# StabTracker.net
KiCad netlist of a schematic drawn in EAGLE
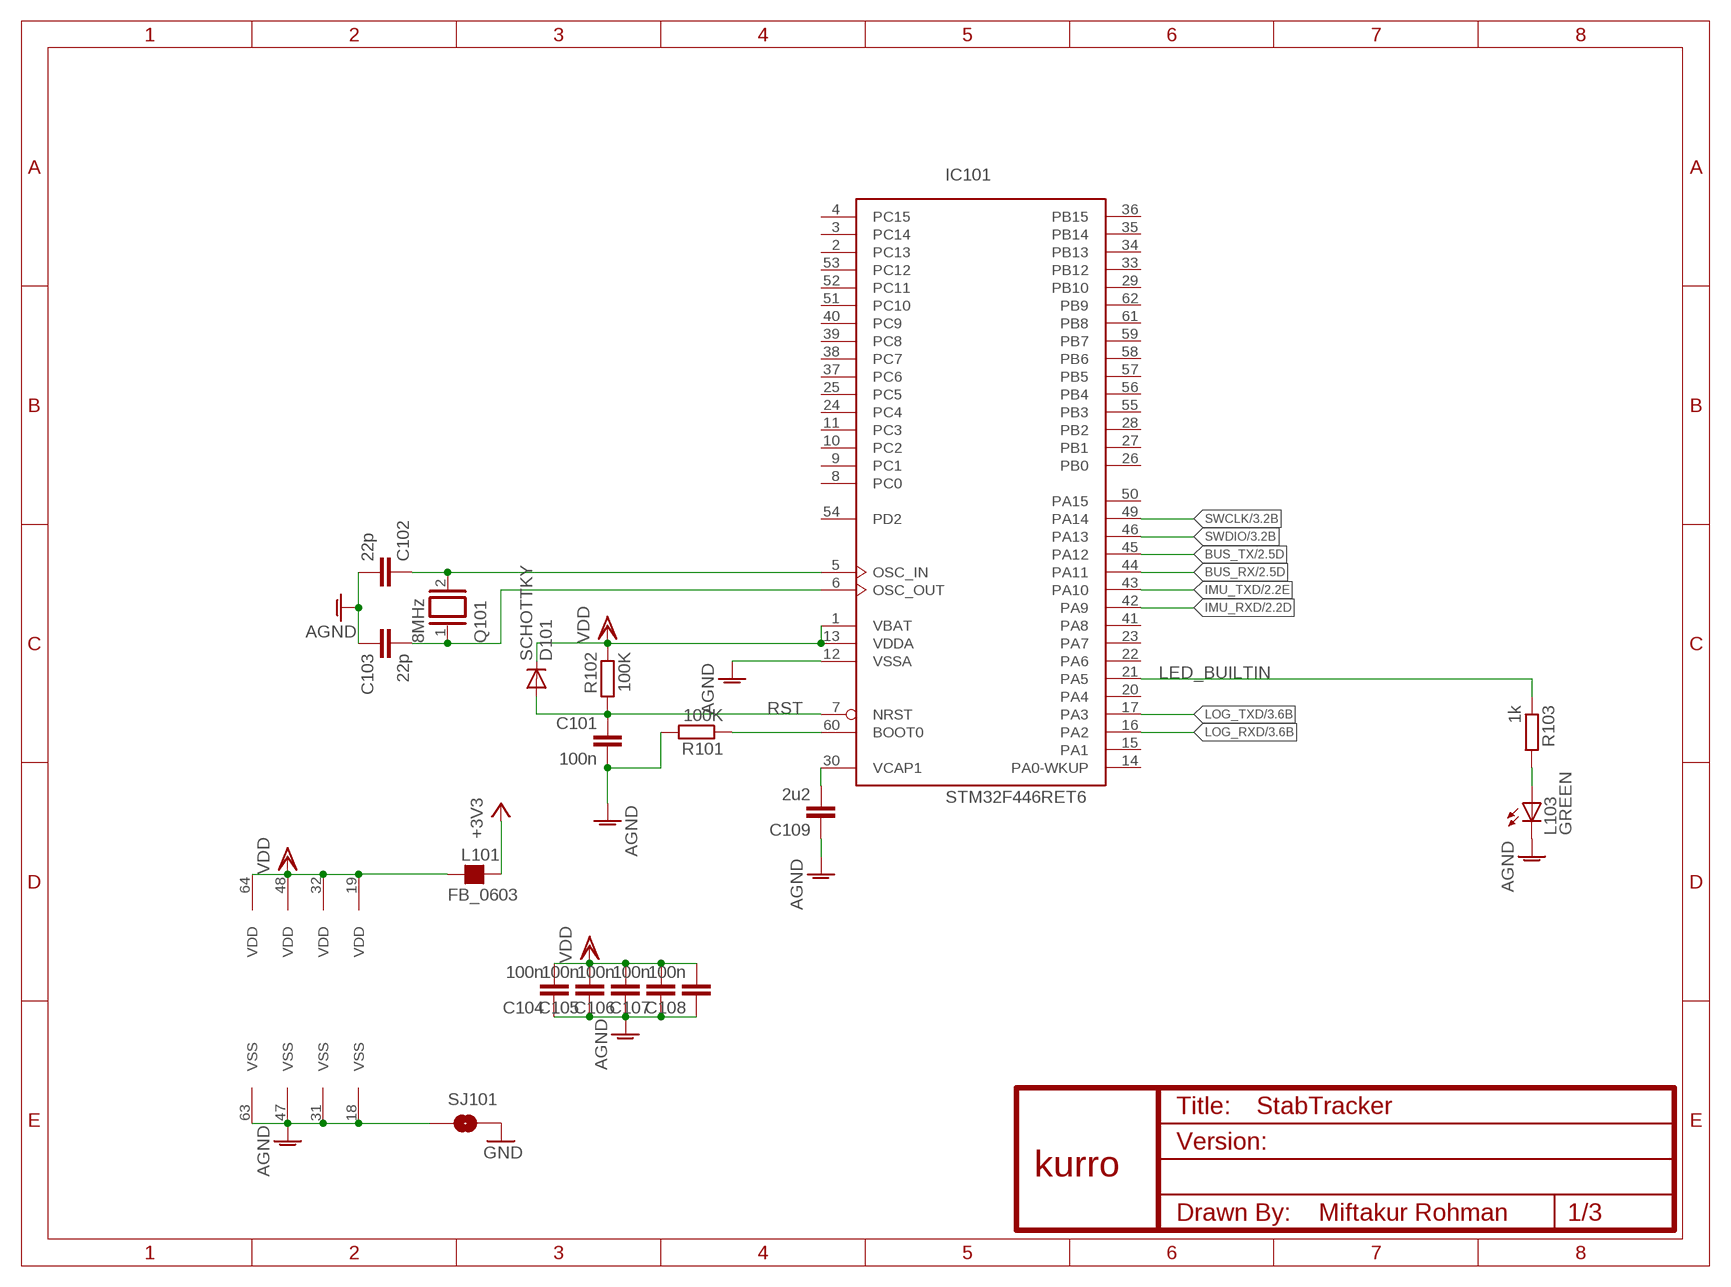
[diagram p0: schematic, sheet 1]
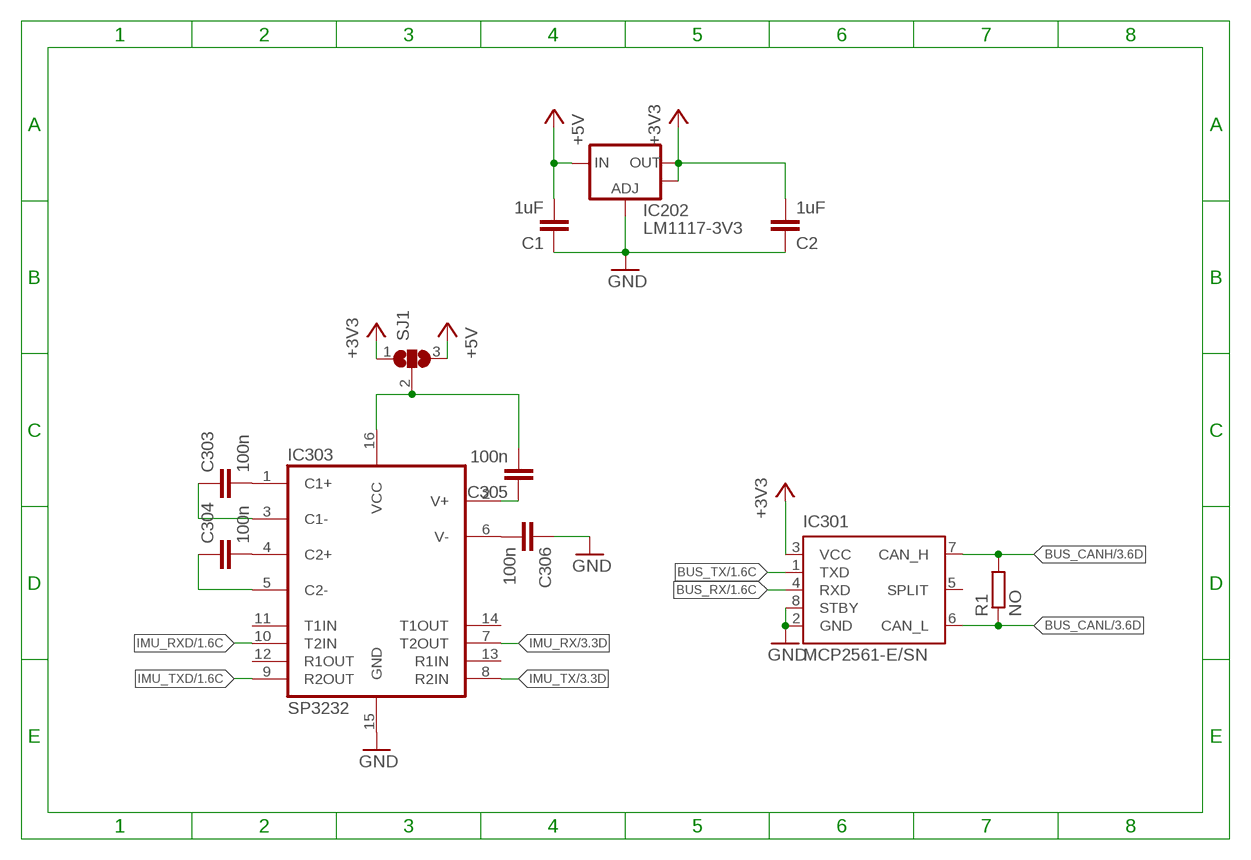
[diagram p1: schematic, sheet 2]
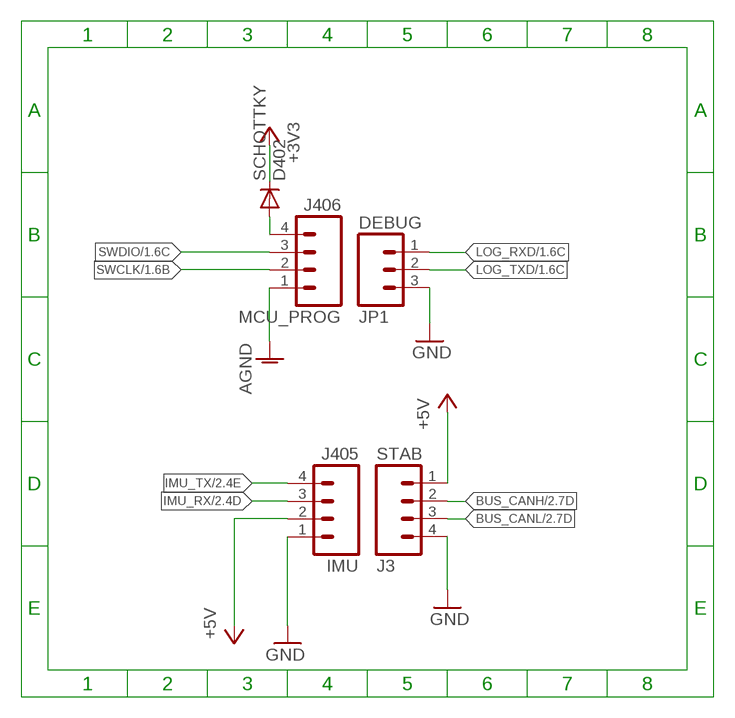
[diagram p2: schematic, sheet 3]

(export (version "E")
  (design (tool "Eeschema 10.0.6"))
  (components
    (comp (ref "D402")
      (value "SCHOTTKY")
      (footprint "eagle-import:MICROMELF-W")
      (libsource (lib "eagle-import") (part "DIODE-MICROMELF-W"))
    )
    (comp (ref "J3")
      (value "STAB")
      (footprint "eagle-import:XH-4-RA")
      (libsource (lib "eagle-import") (part "M04-XH-RA"))
    )
    (comp (ref "J405")
      (value "IMU")
      (footprint "eagle-import:XH-4-RA")
      (libsource (lib "eagle-import") (part "M04-XH-RA"))
    )
    (comp (ref "J406")
      (value "MCU_PROG")
      (footprint "eagle-import:XH-4-RA")
      (libsource (lib "eagle-import") (part "M04-XH-RA"))
    )
    (comp (ref "JP1")
      (value "DEBUG")
      (footprint "eagle-import:XH-3-RA")
      (libsource (lib "eagle-import") (part "M03-XH-RA"))
    )
    (comp (ref "C1")
      (value "1uF")
      (footprint "eagle-import:C0603")
      (libsource (lib "eagle-import") (part "C-EUC0603"))
    )
    (comp (ref "C2")
      (value "1uF")
      (footprint "eagle-import:C0603")
      (libsource (lib "eagle-import") (part "C-EUC0603"))
    )
    (comp (ref "C303")
      (value "100n")
      (footprint "eagle-import:C0603")
      (libsource (lib "eagle-import") (part "C-EUC0603"))
    )
    (comp (ref "C304")
      (value "100n")
      (footprint "eagle-import:C0603")
      (libsource (lib "eagle-import") (part "C-EUC0603"))
    )
    (comp (ref "C305")
      (value "100n")
      (footprint "eagle-import:C0603")
      (libsource (lib "eagle-import") (part "C-EUC0603"))
    )
    (comp (ref "C306")
      (value "100n")
      (footprint "eagle-import:C0603")
      (libsource (lib "eagle-import") (part "C-EUC0603"))
    )
    (comp (ref "IC202")
      (value "LM1117-3V3")
      (footprint "eagle-import:SOT223")
      (libsource (lib "eagle-import") (part "V_REG_LM1117SOT223"))
    )
    (comp (ref "IC301")
      (value "MCP2561-E/SN")
      (footprint "eagle-import:SOIC-8")
      (libsource (lib "eagle-import") (part "MCP2561-E/SN"))
    )
    (comp (ref "IC303")
      (value "SP3232")
      (footprint "eagle-import:SO016")
      (libsource (lib "eagle-import") (part "MAX232SOIC16"))
    )
    (comp (ref "R1")
      (value "NO")
      (footprint "eagle-import:R0603")
      (libsource (lib "eagle-import") (part "R-EU_R0603"))
    )
    (comp (ref "SJ1")
      (value "SJ2W-TRACE")
      (footprint "eagle-import:SJ2")
      (libsource (lib "eagle-import") (part "SJ2W-TRACE"))
    )
    (comp (ref "C101")
      (value "100n")
      (footprint "eagle-import:C0603")
      (libsource (lib "eagle-import") (part "C-EUC0603"))
    )
    (comp (ref "C102")
      (value "22p")
      (footprint "eagle-import:C0603")
      (libsource (lib "eagle-import") (part "C-EUC0603"))
    )
    (comp (ref "C103")
      (value "22p")
      (footprint "eagle-import:C0603")
      (libsource (lib "eagle-import") (part "C-EUC0603"))
    )
    (comp (ref "C104")
      (value "100n")
      (footprint "eagle-import:C0603")
      (libsource (lib "eagle-import") (part "C-EUC0603"))
    )
    (comp (ref "C105")
      (value "100n")
      (footprint "eagle-import:C0603")
      (libsource (lib "eagle-import") (part "C-EUC0603"))
    )
    (comp (ref "C106")
      (value "100n")
      (footprint "eagle-import:C0603")
      (libsource (lib "eagle-import") (part "C-EUC0603"))
    )
    (comp (ref "C107")
      (value "100n")
      (footprint "eagle-import:C0603")
      (libsource (lib "eagle-import") (part "C-EUC0603"))
    )
    (comp (ref "C108")
      (value "100n")
      (footprint "eagle-import:C0603")
      (libsource (lib "eagle-import") (part "C-EUC0603"))
    )
    (comp (ref "C109")
      (value "2u2")
      (footprint "eagle-import:C0603")
      (libsource (lib "eagle-import") (part "C-EUC0603"))
    )
    (comp (ref "D101")
      (value "SCHOTTKY")
      (footprint "eagle-import:MICROMELF-W")
      (libsource (lib "eagle-import") (part "DIODE-MICROMELF-W"))
    )
    (comp (ref "IC101")
      (value "STM32F446RET6")
      (footprint "eagle-import:LQFP64")
      (libsource (lib "eagle-import") (part "STM32F401RTB"))
    )
    (comp (ref "L101")
      (value "FB_0603")
      (footprint "eagle-import:L0603")
      (libsource (lib "eagle-import") (part "FB_0603"))
    )
    (comp (ref "L103")
      (value "GREEN")
      (footprint "eagle-import:CHIP-LED0805")
      (libsource (lib "eagle-import") (part "LEDCHIP-LED0805"))
    )
    (comp (ref "Q101")
      (value "8MHz")
      (footprint "eagle-import:QS")
      (libsource (lib "eagle-import") (part "XTAL/S"))
    )
    (comp (ref "R101")
      (value "100K")
      (footprint "eagle-import:R0603")
      (libsource (lib "eagle-import") (part "R-EU_R0603"))
    )
    (comp (ref "R102")
      (value "100K")
      (footprint "eagle-import:R0603")
      (libsource (lib "eagle-import") (part "R-EU_R0603"))
    )
    (comp (ref "R103")
      (value "1k")
      (footprint "eagle-import:R0603")
      (libsource (lib "eagle-import") (part "R-EU_R0603"))
    )
    (comp (ref "SJ101")
      (value "SOLDERJUMPERTRACE")
      (footprint "eagle-import:SJ_2S-TRACE")
      (libsource (lib "eagle-import") (part "SOLDERJUMPERTRACE"))
    )
    (comp (ref "U$1")
      (value "KURRO_FOOTPRINT")
      (footprint "eagle-import:KURRO-LOGO")
      (libsource (lib "eagle-import") (part "KURRO_FOOTPRINT"))
    )
  )
  (nets
    (net (code "1") (name "+3V3") (class "Default")
      (node (ref "C2") (pin "2") (pinfunction "2_2") (pintype "passive"))
      (node (ref "D402") (pin "C") (pinfunction "C_C") (pintype "passive"))
      (node (ref "IC202") (pin "2") (pinfunction "OUT_2") (pintype "power_in"))
      (node (ref "IC202") (pin "4") (pinfunction "OUT_4") (pintype "power_in"))
      (node (ref "IC301") (pin "3") (pinfunction "VCC_3") (pintype "bidirectional"))
      (node (ref "L101") (pin "2") (pinfunction "2_2") (pintype "passive"))
      (node (ref "SJ1") (pin "1") (pinfunction "1_1") (pintype "passive"))
    )
    (net (code "2") (name "+5V") (class "Default")
      (node (ref "C1") (pin "2") (pinfunction "2_2") (pintype "passive"))
      (node (ref "IC202") (pin "3") (pinfunction "IN_3") (pintype "input"))
      (node (ref "J3") (pin "1") (pinfunction "1_1") (pintype "passive"))
      (node (ref "J405") (pin "2") (pinfunction "2_2") (pintype "passive"))
      (node (ref "SJ1") (pin "3") (pinfunction "3_3") (pintype "passive"))
    )
    (net (code "3") (name "AGND") (class "Default")
      (node (ref "C101") (pin "2") (pinfunction "2_2") (pintype "passive"))
      (node (ref "C102") (pin "2") (pinfunction "2_2") (pintype "passive"))
      (node (ref "C103") (pin "1") (pinfunction "1_1") (pintype "passive"))
      (node (ref "C104") (pin "1") (pinfunction "1_1") (pintype "passive"))
      (node (ref "C105") (pin "1") (pinfunction "1_1") (pintype "passive"))
      (node (ref "C106") (pin "1") (pinfunction "1_1") (pintype "passive"))
      (node (ref "C107") (pin "1") (pinfunction "1_1") (pintype "passive"))
      (node (ref "C108") (pin "1") (pinfunction "1_1") (pintype "passive"))
      (node (ref "C109") (pin "1") (pinfunction "1_1") (pintype "passive"))
      (node (ref "IC101") (pin "12") (pinfunction "VSSA_12") (pintype "power_in"))
      (node (ref "IC101") (pin "18") (pinfunction "VSS_18") (pintype "power_in"))
      (node (ref "IC101") (pin "31") (pinfunction "VSS_31") (pintype "power_in"))
      (node (ref "IC101") (pin "47") (pinfunction "VSS_47") (pintype "power_in"))
      (node (ref "IC101") (pin "63") (pinfunction "VSS_63") (pintype "power_in"))
      (node (ref "J406") (pin "1") (pinfunction "1_1") (pintype "passive"))
      (node (ref "L103") (pin "C") (pinfunction "C_C") (pintype "passive"))
      (node (ref "R101") (pin "2") (pinfunction "2_2") (pintype "passive"))
      (node (ref "SJ101") (pin "1") (pinfunction "1_1") (pintype "passive"))
    )
    (net (code "4") (name "BUS_CANH") (class "Default")
      (node (ref "IC301") (pin "7") (pinfunction "CAN_H_7") (pintype "bidirectional"))
      (node (ref "J3") (pin "2") (pinfunction "2_2") (pintype "passive"))
      (node (ref "R1") (pin "2") (pinfunction "2_2") (pintype "passive"))
    )
    (net (code "5") (name "BUS_CANL") (class "Default")
      (node (ref "IC301") (pin "6") (pinfunction "CAN_L_6") (pintype "bidirectional"))
      (node (ref "J3") (pin "3") (pinfunction "3_3") (pintype "passive"))
      (node (ref "R1") (pin "1") (pinfunction "1_1") (pintype "passive"))
    )
    (net (code "6") (name "BUS_RX") (class "Default")
      (node (ref "IC101") (pin "44") (pinfunction "PA11_44") (pintype "bidirectional"))
      (node (ref "IC301") (pin "4") (pinfunction "RXD_4") (pintype "bidirectional"))
    )
    (net (code "7") (name "BUS_TX") (class "Default")
      (node (ref "IC101") (pin "45") (pinfunction "PA12_45") (pintype "bidirectional"))
      (node (ref "IC301") (pin "1") (pinfunction "TXD_1") (pintype "bidirectional"))
    )
    (net (code "8") (name "GND") (class "Default")
      (node (ref "C1") (pin "1") (pinfunction "1_1") (pintype "passive"))
      (node (ref "C2") (pin "1") (pinfunction "1_1") (pintype "passive"))
      (node (ref "C306") (pin "1") (pinfunction "1_1") (pintype "passive"))
      (node (ref "IC202") (pin "1") (pinfunction "ADJ_1") (pintype "input"))
      (node (ref "IC301") (pin "2") (pinfunction "GND_2") (pintype "bidirectional"))
      (node (ref "IC301") (pin "8") (pinfunction "STBY_8") (pintype "bidirectional"))
      (node (ref "IC303") (pin "15") (pinfunction "GND_15") (pintype "bidirectional"))
      (node (ref "J3") (pin "4") (pinfunction "4_4") (pintype "passive"))
      (node (ref "J405") (pin "1") (pinfunction "1_1") (pintype "passive"))
      (node (ref "JP1") (pin "3") (pinfunction "3_3") (pintype "passive"))
      (node (ref "SJ101") (pin "2") (pinfunction "2_2") (pintype "passive"))
    )
    (net (code "9") (name "IMU_RX") (class "Default")
      (node (ref "IC303") (pin "7") (pinfunction "T2OUT_7") (pintype "output"))
      (node (ref "J405") (pin "3") (pinfunction "3_3") (pintype "passive"))
    )
    (net (code "10") (name "IMU_RXD") (class "Default")
      (node (ref "IC101") (pin "42") (pinfunction "PA9_42") (pintype "bidirectional"))
      (node (ref "IC303") (pin "10") (pinfunction "T2IN_10") (pintype "input"))
    )
    (net (code "11") (name "IMU_TX") (class "Default")
      (node (ref "IC303") (pin "8") (pinfunction "R2IN_8") (pintype "input"))
      (node (ref "J405") (pin "4") (pinfunction "4_4") (pintype "passive"))
    )
    (net (code "12") (name "IMU_TXD") (class "Default")
      (node (ref "IC101") (pin "43") (pinfunction "PA10_43") (pintype "bidirectional"))
      (node (ref "IC303") (pin "9") (pinfunction "R2OUT_9") (pintype "output"))
    )
    (net (code "13") (name "LED_BUILTIN") (class "Default")
      (node (ref "IC101") (pin "21") (pinfunction "PA5_21") (pintype "bidirectional"))
      (node (ref "R103") (pin "1") (pinfunction "1_1") (pintype "passive"))
    )
    (net (code "14") (name "LOG_RXD") (class "Default")
      (node (ref "IC101") (pin "16") (pinfunction "PA2_16") (pintype "bidirectional"))
      (node (ref "JP1") (pin "1") (pinfunction "1_1") (pintype "passive"))
    )
    (net (code "15") (name "LOG_TXD") (class "Default")
      (node (ref "IC101") (pin "17") (pinfunction "PA3_17") (pintype "bidirectional"))
      (node (ref "JP1") (pin "2") (pinfunction "2_2") (pintype "passive"))
    )
    (net (code "16") (name "Net-(D402-PadA)") (class "Default")
      (node (ref "D402") (pin "A") (pinfunction "A_A") (pintype "passive"))
      (node (ref "J406") (pin "4") (pinfunction "4_4") (pintype "passive"))
    )
    (net (code "17") (name "Net-(IC101A-BOOT0)") (class "Default")
      (node (ref "IC101") (pin "60") (pinfunction "BOOT0_60") (pintype "input"))
      (node (ref "R101") (pin "1") (pinfunction "1_1") (pintype "passive"))
    )
    (net (code "18") (name "Net-(IC101A-OSC_IN)") (class "Default")
      (node (ref "C102") (pin "1") (pinfunction "1_1") (pintype "passive"))
      (node (ref "IC101") (pin "5") (pinfunction "OSC_IN_5") (pintype "bidirectional"))
      (node (ref "Q101") (pin "2") (pinfunction "2_2") (pintype "passive"))
    )
    (net (code "19") (name "Net-(IC101A-OSC_OUT)") (class "Default")
      (node (ref "C103") (pin "2") (pinfunction "2_2") (pintype "passive"))
      (node (ref "IC101") (pin "6") (pinfunction "OSC_OUT_6") (pintype "bidirectional"))
      (node (ref "Q101") (pin "1") (pinfunction "1_1") (pintype "passive"))
    )
    (net (code "20") (name "Net-(IC101A-VCAP1)") (class "Default")
      (node (ref "C109") (pin "2") (pinfunction "2_2") (pintype "passive"))
      (node (ref "IC101") (pin "30") (pinfunction "VCAP1_30") (pintype "power_in"))
    )
    (net (code "21") (name "Net-(IC303-C1+)") (class "Default")
      (node (ref "C303") (pin "2") (pinfunction "2_2") (pintype "passive"))
      (node (ref "IC303") (pin "1") (pinfunction "C1+_1") (pintype "bidirectional"))
    )
    (net (code "22") (name "Net-(IC303-C1-)") (class "Default")
      (node (ref "C303") (pin "1") (pinfunction "1_1") (pintype "passive"))
      (node (ref "IC303") (pin "3") (pinfunction "C1-_3") (pintype "bidirectional"))
    )
    (net (code "23") (name "Net-(IC303-C2+)") (class "Default")
      (node (ref "C304") (pin "2") (pinfunction "2_2") (pintype "passive"))
      (node (ref "IC303") (pin "4") (pinfunction "C2+_4") (pintype "bidirectional"))
    )
    (net (code "24") (name "Net-(IC303-C2-)") (class "Default")
      (node (ref "C304") (pin "1") (pinfunction "1_1") (pintype "passive"))
      (node (ref "IC303") (pin "5") (pinfunction "C2-_5") (pintype "bidirectional"))
    )
    (net (code "25") (name "Net-(IC303-V+)") (class "Default")
      (node (ref "C305") (pin "1") (pinfunction "1_1") (pintype "passive"))
      (node (ref "IC303") (pin "2") (pinfunction "V+_2") (pintype "bidirectional"))
    )
    (net (code "26") (name "Net-(IC303-V-)") (class "Default")
      (node (ref "C306") (pin "2") (pinfunction "2_2") (pintype "passive"))
      (node (ref "IC303") (pin "6") (pinfunction "V-_6") (pintype "bidirectional"))
    )
    (net (code "27") (name "Net-(IC303-VCC)") (class "Default")
      (node (ref "C305") (pin "2") (pinfunction "2_2") (pintype "passive"))
      (node (ref "IC303") (pin "16") (pinfunction "VCC_16") (pintype "bidirectional"))
      (node (ref "SJ1") (pin "2") (pinfunction "2_2") (pintype "passive"))
    )
    (net (code "28") (name "Net-(L103-PadA)") (class "Default")
      (node (ref "L103") (pin "A") (pinfunction "A_A") (pintype "passive"))
      (node (ref "R103") (pin "2") (pinfunction "2_2") (pintype "passive"))
    )
    (net (code "29") (name "RST") (class "Default")
      (node (ref "C101") (pin "1") (pinfunction "1_1") (pintype "passive"))
      (node (ref "D101") (pin "A") (pinfunction "A_A") (pintype "passive"))
      (node (ref "IC101") (pin "7") (pinfunction "NRST_7") (pintype "bidirectional"))
      (node (ref "R102") (pin "2") (pinfunction "2_2") (pintype "passive"))
    )
    (net (code "30") (name "SWCLK") (class "Default")
      (node (ref "IC101") (pin "49") (pinfunction "PA14_49") (pintype "bidirectional"))
      (node (ref "J406") (pin "2") (pinfunction "2_2") (pintype "passive"))
    )
    (net (code "31") (name "SWDIO") (class "Default")
      (node (ref "IC101") (pin "46") (pinfunction "PA13_46") (pintype "bidirectional"))
      (node (ref "J406") (pin "3") (pinfunction "3_3") (pintype "passive"))
    )
    (net (code "32") (name "VDD") (class "Default")
      (node (ref "C104") (pin "2") (pinfunction "2_2") (pintype "passive"))
      (node (ref "C105") (pin "2") (pinfunction "2_2") (pintype "passive"))
      (node (ref "C106") (pin "2") (pinfunction "2_2") (pintype "passive"))
      (node (ref "C107") (pin "2") (pinfunction "2_2") (pintype "passive"))
      (node (ref "C108") (pin "2") (pinfunction "2_2") (pintype "passive"))
      (node (ref "D101") (pin "C") (pinfunction "C_C") (pintype "passive"))
      (node (ref "IC101") (pin "1") (pinfunction "VBAT_1") (pintype "power_in"))
      (node (ref "IC101") (pin "13") (pinfunction "VDDA_13") (pintype "power_in"))
      (node (ref "IC101") (pin "19") (pinfunction "VDD_19") (pintype "power_in"))
      (node (ref "IC101") (pin "32") (pinfunction "VDD_32") (pintype "power_in"))
      (node (ref "IC101") (pin "48") (pinfunction "VDD_48") (pintype "power_in"))
      (node (ref "IC101") (pin "64") (pinfunction "VDD_64") (pintype "power_in"))
      (node (ref "L101") (pin "1") (pinfunction "1_1") (pintype "passive"))
      (node (ref "R102") (pin "1") (pinfunction "1_1") (pintype "passive"))
    )
    (net (code "33") (name "unconnected-(IC101A-PA0-WKUP-Pad14)") (class "Default")
      (node (ref "IC101") (pin "14") (pinfunction "PA0-WKUP_14") (pintype "bidirectional"))
    )
    (net (code "34") (name "unconnected-(IC101A-PA1-Pad15)") (class "Default")
      (node (ref "IC101") (pin "15") (pinfunction "PA1_15") (pintype "bidirectional"))
    )
    (net (code "35") (name "unconnected-(IC101A-PA4-Pad20)") (class "Default")
      (node (ref "IC101") (pin "20") (pinfunction "PA4_20") (pintype "bidirectional"))
    )
    (net (code "36") (name "unconnected-(IC101A-PA6-Pad22)") (class "Default")
      (node (ref "IC101") (pin "22") (pinfunction "PA6_22") (pintype "bidirectional"))
    )
    (net (code "37") (name "unconnected-(IC101A-PA7-Pad23)") (class "Default")
      (node (ref "IC101") (pin "23") (pinfunction "PA7_23") (pintype "bidirectional"))
    )
    (net (code "38") (name "unconnected-(IC101A-PA8-Pad41)") (class "Default")
      (node (ref "IC101") (pin "41") (pinfunction "PA8_41") (pintype "bidirectional"))
    )
    (net (code "39") (name "unconnected-(IC101A-PA15-Pad50)") (class "Default")
      (node (ref "IC101") (pin "50") (pinfunction "PA15_50") (pintype "bidirectional"))
    )
    (net (code "40") (name "unconnected-(IC101A-PB0-Pad26)") (class "Default")
      (node (ref "IC101") (pin "26") (pinfunction "PB0_26") (pintype "bidirectional"))
    )
    (net (code "41") (name "unconnected-(IC101A-PB1-Pad27)") (class "Default")
      (node (ref "IC101") (pin "27") (pinfunction "PB1_27") (pintype "bidirectional"))
    )
    (net (code "42") (name "unconnected-(IC101A-PB2-Pad28)") (class "Default")
      (node (ref "IC101") (pin "28") (pinfunction "PB2_28") (pintype "bidirectional"))
    )
    (net (code "43") (name "unconnected-(IC101A-PB3-Pad55)") (class "Default")
      (node (ref "IC101") (pin "55") (pinfunction "PB3_55") (pintype "bidirectional"))
    )
    (net (code "44") (name "unconnected-(IC101A-PB4-Pad56)") (class "Default")
      (node (ref "IC101") (pin "56") (pinfunction "PB4_56") (pintype "bidirectional"))
    )
    (net (code "45") (name "unconnected-(IC101A-PB5-Pad57)") (class "Default")
      (node (ref "IC101") (pin "57") (pinfunction "PB5_57") (pintype "bidirectional"))
    )
    (net (code "46") (name "unconnected-(IC101A-PB6-Pad58)") (class "Default")
      (node (ref "IC101") (pin "58") (pinfunction "PB6_58") (pintype "bidirectional"))
    )
    (net (code "47") (name "unconnected-(IC101A-PB7-Pad59)") (class "Default")
      (node (ref "IC101") (pin "59") (pinfunction "PB7_59") (pintype "bidirectional"))
    )
    (net (code "48") (name "unconnected-(IC101A-PB8-Pad61)") (class "Default")
      (node (ref "IC101") (pin "61") (pinfunction "PB8_61") (pintype "bidirectional"))
    )
    (net (code "49") (name "unconnected-(IC101A-PB9-Pad62)") (class "Default")
      (node (ref "IC101") (pin "62") (pinfunction "PB9_62") (pintype "bidirectional"))
    )
    (net (code "50") (name "unconnected-(IC101A-PB10-Pad29)") (class "Default")
      (node (ref "IC101") (pin "29") (pinfunction "PB10_29") (pintype "bidirectional"))
    )
    (net (code "51") (name "unconnected-(IC101A-PB12-Pad33)") (class "Default")
      (node (ref "IC101") (pin "33") (pinfunction "PB12_33") (pintype "bidirectional"))
    )
    (net (code "52") (name "unconnected-(IC101A-PB13-Pad34)") (class "Default")
      (node (ref "IC101") (pin "34") (pinfunction "PB13_34") (pintype "bidirectional"))
    )
    (net (code "53") (name "unconnected-(IC101A-PB14-Pad35)") (class "Default")
      (node (ref "IC101") (pin "35") (pinfunction "PB14_35") (pintype "bidirectional"))
    )
    (net (code "54") (name "unconnected-(IC101A-PB15-Pad36)") (class "Default")
      (node (ref "IC101") (pin "36") (pinfunction "PB15_36") (pintype "bidirectional"))
    )
    (net (code "55") (name "unconnected-(IC101A-PC0-Pad8)") (class "Default")
      (node (ref "IC101") (pin "8") (pinfunction "PC0_8") (pintype "bidirectional"))
    )
    (net (code "56") (name "unconnected-(IC101A-PC1-Pad9)") (class "Default")
      (node (ref "IC101") (pin "9") (pinfunction "PC1_9") (pintype "bidirectional"))
    )
    (net (code "57") (name "unconnected-(IC101A-PC2-Pad10)") (class "Default")
      (node (ref "IC101") (pin "10") (pinfunction "PC2_10") (pintype "bidirectional"))
    )
    (net (code "58") (name "unconnected-(IC101A-PC3-Pad11)") (class "Default")
      (node (ref "IC101") (pin "11") (pinfunction "PC3_11") (pintype "bidirectional"))
    )
    (net (code "59") (name "unconnected-(IC101A-PC4-Pad24)") (class "Default")
      (node (ref "IC101") (pin "24") (pinfunction "PC4_24") (pintype "bidirectional"))
    )
    (net (code "60") (name "unconnected-(IC101A-PC5-Pad25)") (class "Default")
      (node (ref "IC101") (pin "25") (pinfunction "PC5_25") (pintype "bidirectional"))
    )
    (net (code "61") (name "unconnected-(IC101A-PC6-Pad37)") (class "Default")
      (node (ref "IC101") (pin "37") (pinfunction "PC6_37") (pintype "bidirectional"))
    )
    (net (code "62") (name "unconnected-(IC101A-PC7-Pad38)") (class "Default")
      (node (ref "IC101") (pin "38") (pinfunction "PC7_38") (pintype "bidirectional"))
    )
    (net (code "63") (name "unconnected-(IC101A-PC8-Pad39)") (class "Default")
      (node (ref "IC101") (pin "39") (pinfunction "PC8_39") (pintype "bidirectional"))
    )
    (net (code "64") (name "unconnected-(IC101A-PC9-Pad40)") (class "Default")
      (node (ref "IC101") (pin "40") (pinfunction "PC9_40") (pintype "bidirectional"))
    )
    (net (code "65") (name "unconnected-(IC101A-PC10-Pad51)") (class "Default")
      (node (ref "IC101") (pin "51") (pinfunction "PC10_51") (pintype "bidirectional"))
    )
    (net (code "66") (name "unconnected-(IC101A-PC11-Pad52)") (class "Default")
      (node (ref "IC101") (pin "52") (pinfunction "PC11_52") (pintype "bidirectional"))
    )
    (net (code "67") (name "unconnected-(IC101A-PC12-Pad53)") (class "Default")
      (node (ref "IC101") (pin "53") (pinfunction "PC12_53") (pintype "bidirectional"))
    )
    (net (code "68") (name "unconnected-(IC101A-PC13-Pad2)") (class "Default")
      (node (ref "IC101") (pin "2") (pinfunction "PC13_2") (pintype "bidirectional"))
    )
    (net (code "69") (name "unconnected-(IC101A-PC14-Pad3)") (class "Default")
      (node (ref "IC101") (pin "3") (pinfunction "PC14_3") (pintype "bidirectional"))
    )
    (net (code "70") (name "unconnected-(IC101A-PC15-Pad4)") (class "Default")
      (node (ref "IC101") (pin "4") (pinfunction "PC15_4") (pintype "bidirectional"))
    )
    (net (code "71") (name "unconnected-(IC101A-PD2-Pad54)") (class "Default")
      (node (ref "IC101") (pin "54") (pinfunction "PD2_54") (pintype "bidirectional"))
    )
    (net (code "72") (name "unconnected-(IC301-SPLIT-Pad5)") (class "Default")
      (node (ref "IC301") (pin "5") (pinfunction "SPLIT_5") (pintype "bidirectional"))
    )
    (net (code "73") (name "unconnected-(IC303-R1IN-Pad13)") (class "Default")
      (node (ref "IC303") (pin "13") (pinfunction "R1IN_13") (pintype "input"))
    )
    (net (code "74") (name "unconnected-(IC303-R1OUT-Pad12)") (class "Default")
      (node (ref "IC303") (pin "12") (pinfunction "R1OUT_12") (pintype "output"))
    )
    (net (code "75") (name "unconnected-(IC303-T1IN-Pad11)") (class "Default")
      (node (ref "IC303") (pin "11") (pinfunction "T1IN_11") (pintype "input"))
    )
    (net (code "76") (name "unconnected-(IC303-T1OUT-Pad14)") (class "Default")
      (node (ref "IC303") (pin "14") (pinfunction "T1OUT_14") (pintype "output"))
    )
  )
)
